# STC8a.net
KiCad netlist of a schematic drawn in Altium Designer
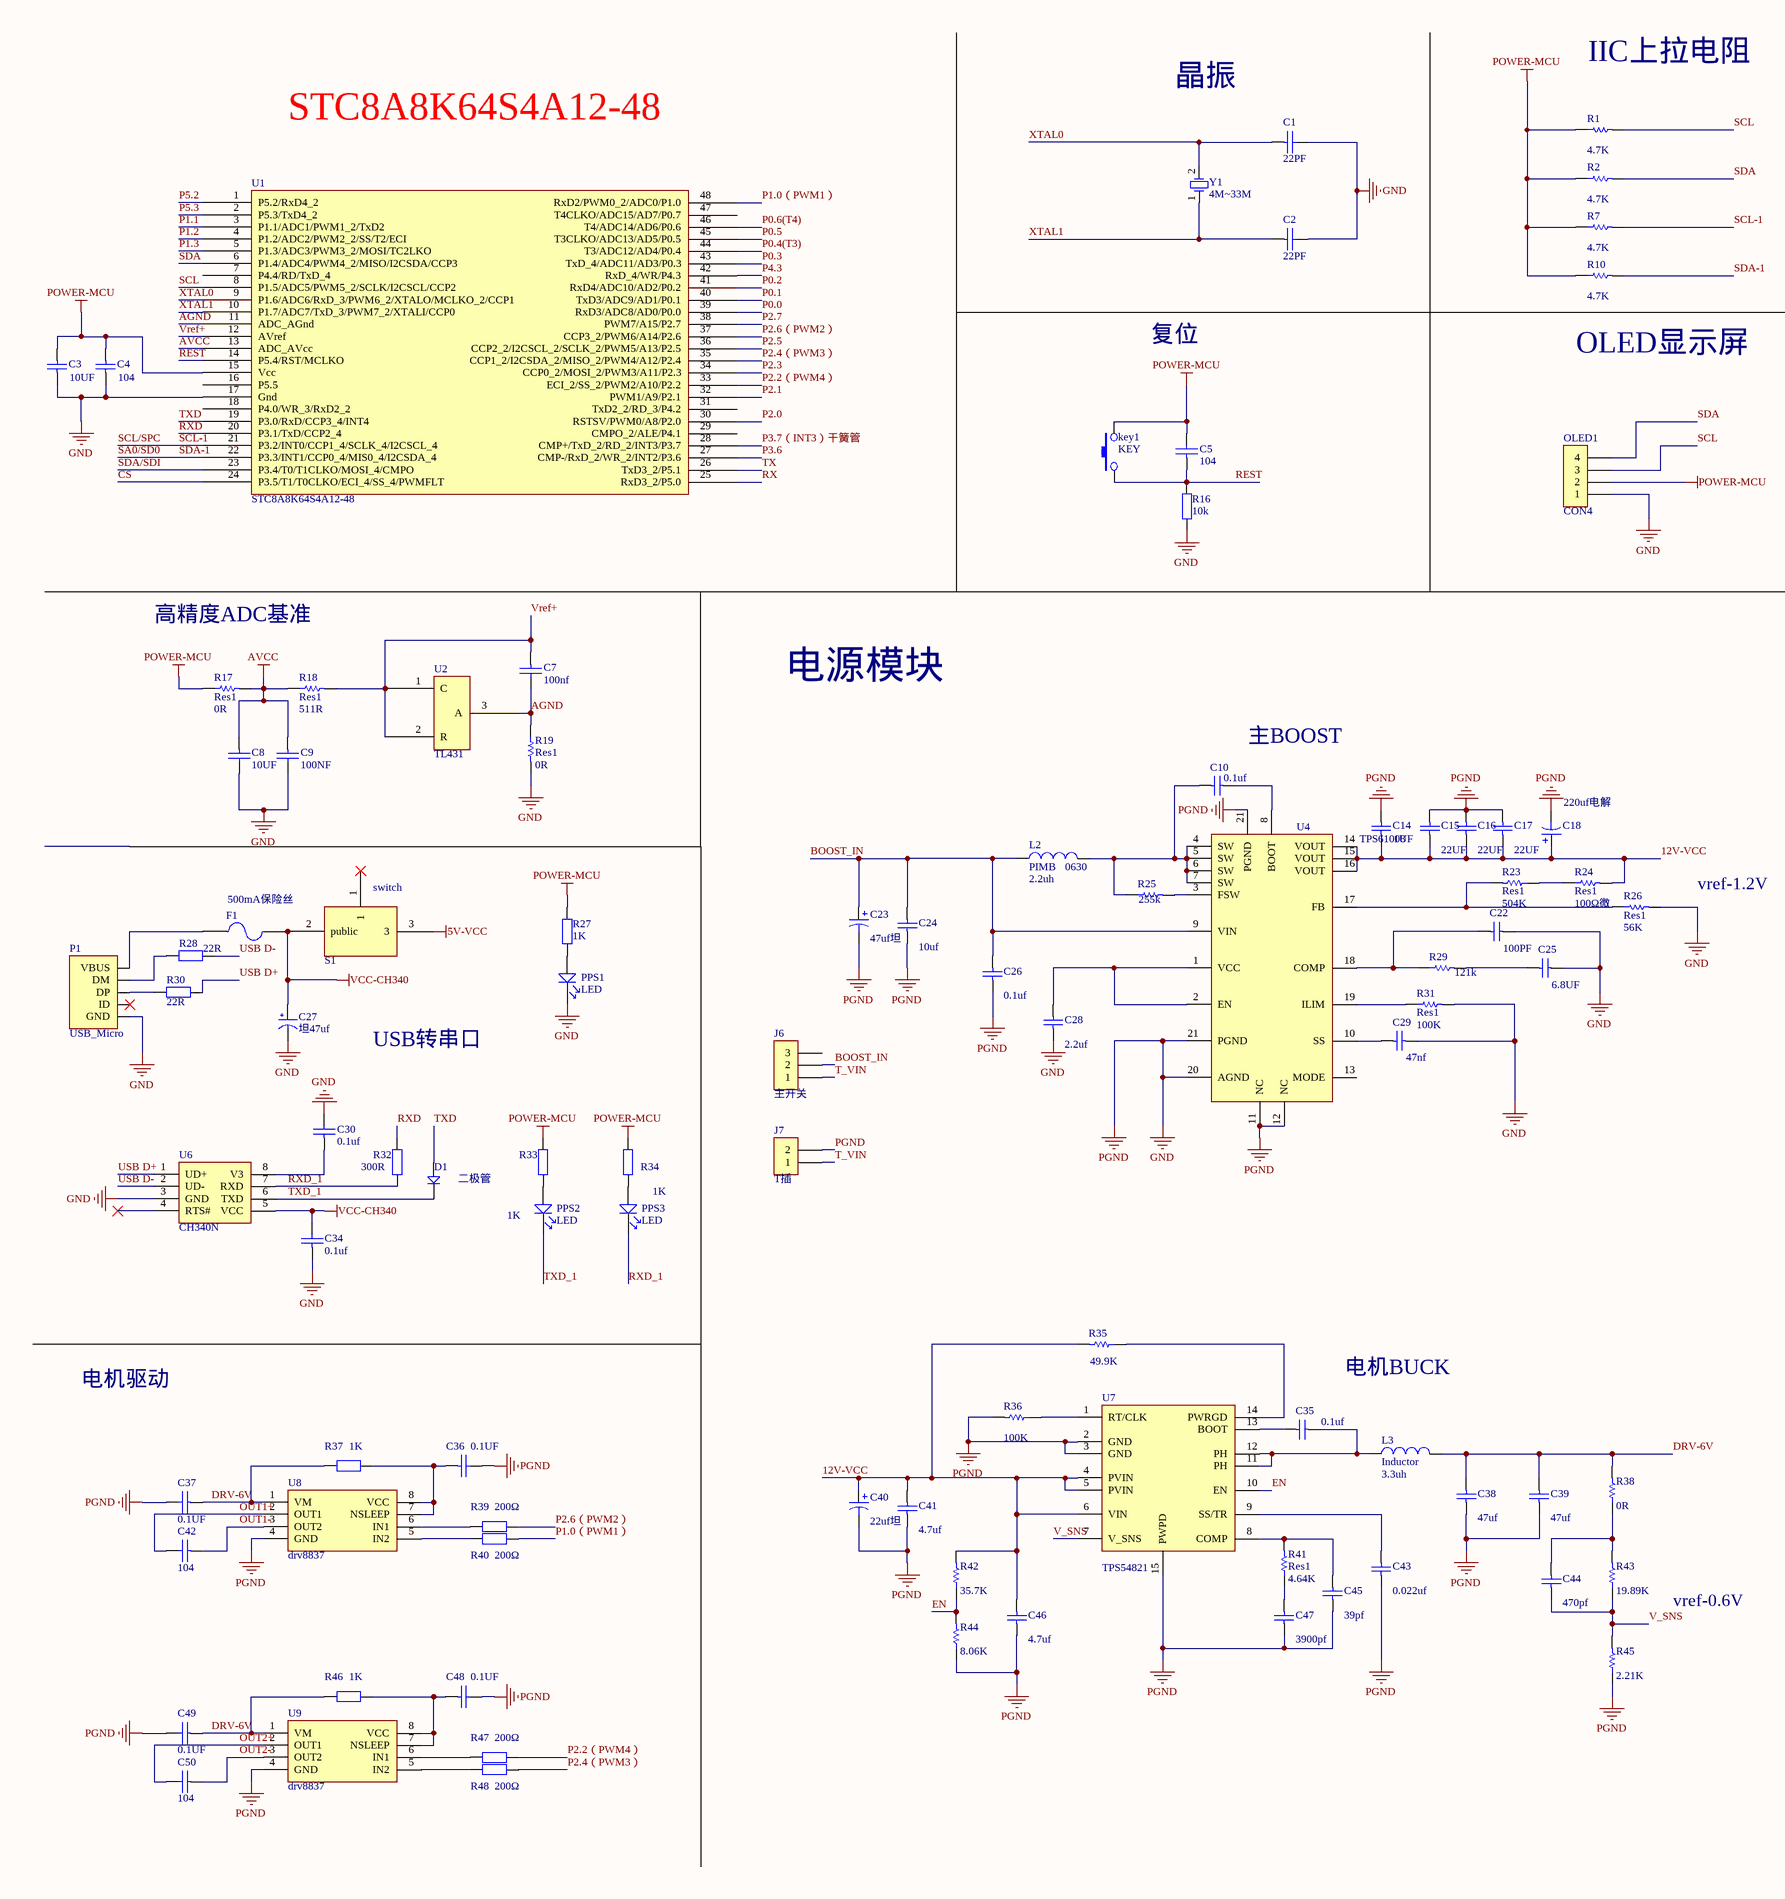
[diagram p0: STC8a.SchDoc, left]
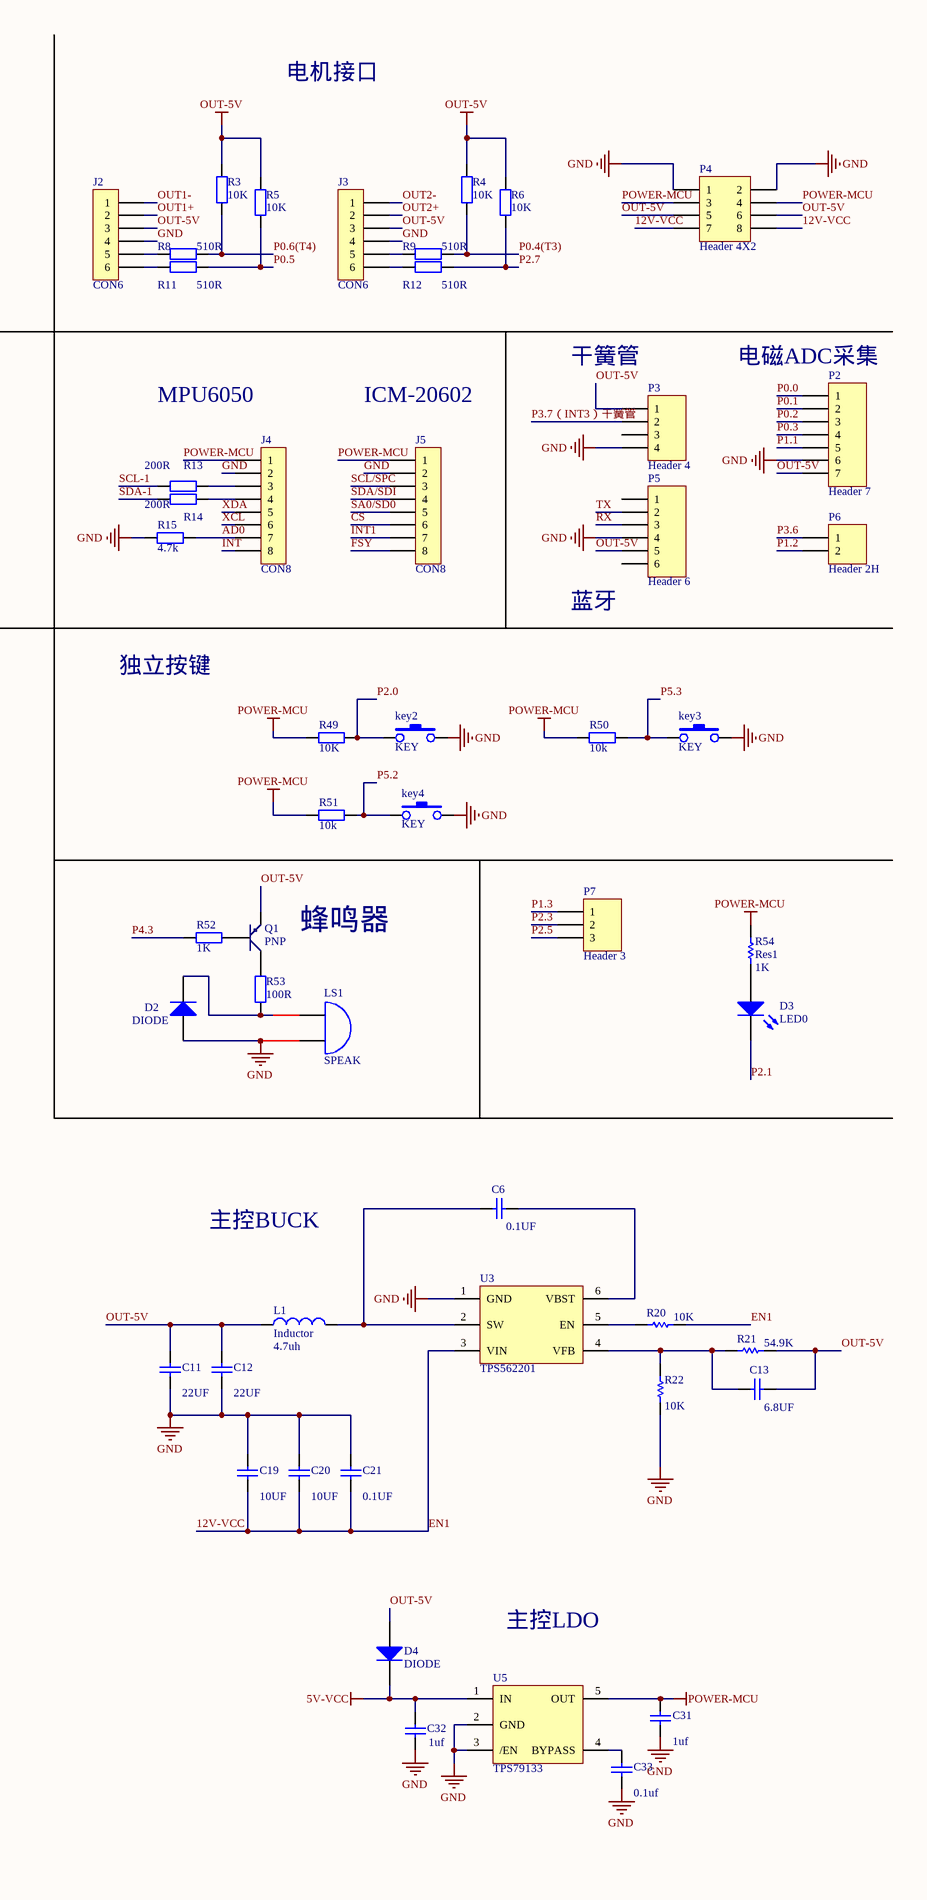
[diagram p1: STC8a.SchDoc, right]

(export (version "E")
  (design (tool "Eeschema 10.0.6"))
  (components
    (comp (ref "C1") (value "22PF") (footprint "0603-C") (libsource (lib "XH-Library") (part "CAP_0805")))
    (comp (ref "C2") (value "22PF") (footprint "0603-C") (libsource (lib "XH-Library") (part "CAP_0805")))
    (comp (ref "C3")
      (value "10UF")
      (footprint "0603-C")
      (description "Capacitor")
      (fields (field (name "PUBLISHER") "Altium Limited"))
      (libsource (lib "Miscellaneous Devices") (part "Cap"))
    )
    (comp (ref "C4")
      (value "104")
      (footprint "0603-C")
      (description "Capacitor")
      (fields (field (name "PUBLISHER") "Altium Limited"))
      (libsource (lib "Miscellaneous Devices") (part "Cap"))
    )
    (comp (ref "C5") (value "104") (footprint "0603-C") (libsource (lib "MINE") (part "CAP_0805")))
    (comp (ref "C6")
      (value "0.1UF")
      (footprint "0603-c")
      (description "Capacitor")
      (fields (field (name "PUBLISHER") "Altium Limited"))
      (libsource (lib "Miscellaneous Devices") (part "Cap"))
    )
    (comp (ref "C7") (value "100nf") (footprint "0603-C") (libsource (lib "自创(1)(1)") (part "CAP")))
    (comp (ref "C8") (value "10UF") (footprint "0603-C") (libsource (lib "自创(1)(1)") (part "CAP")))
    (comp (ref "C9") (value "100NF") (footprint "0603-C") (libsource (lib "自创(1)(1)") (part "CAP")))
    (comp (ref "C10")
      (value "0.1uf")
      (footprint "0603-c")
      (description "Capacitor")
      (fields (field (name "PUBLISHER") "Altium Limited"))
      (libsource (lib "Miscellaneous Devices") (part "Cap"))
    )
    (comp (ref "C11")
      (value "22UF")
      (footprint "1206")
      (description "Capacitor")
      (fields (field (name "PUBLISHER") "Altium Limited"))
      (libsource (lib "Miscellaneous Devices") (part "Cap"))
    )
    (comp (ref "C12")
      (value "22UF")
      (footprint "1206")
      (description "Capacitor")
      (fields (field (name "PUBLISHER") "Altium Limited"))
      (libsource (lib "Miscellaneous Devices") (part "Cap"))
    )
    (comp (ref "C13")
      (value "6.8UF")
      (footprint "0603-c")
      (description "Capacitor")
      (fields (field (name "PUBLISHER") "Altium Limited"))
      (libsource (lib "Miscellaneous Devices") (part "Cap"))
    )
    (comp (ref "C14")
      (value "1UF")
      (footprint "0805C")
      (description "Capacitor")
      (fields (field (name "PUBLISHER") "Altium Limited"))
      (libsource (lib "Miscellaneous Devices") (part "Cap"))
    )
    (comp (ref "C15")
      (value "22UF")
      (footprint "1206")
      (description "Capacitor")
      (fields (field (name "PUBLISHER") "Altium Limited"))
      (libsource (lib "Miscellaneous Devices") (part "Cap"))
    )
    (comp (ref "C16")
      (value "22UF")
      (footprint "1206")
      (description "Capacitor")
      (fields (field (name "PUBLISHER") "Altium Limited"))
      (libsource (lib "Miscellaneous Devices") (part "Cap"))
    )
    (comp (ref "C17")
      (value "22UF")
      (footprint "1206")
      (description "Capacitor")
      (fields (field (name "PUBLISHER") "Altium Limited"))
      (libsource (lib "Miscellaneous Devices") (part "Cap"))
    )
    (comp (ref "C18")
      (value "220uf电解")
      (footprint "CC88")
      (description "Polarized Capacitor (Radial)")
      (fields (field (name "PUBLISHER") "Altium Limited"))
      (libsource (lib "Miscellaneous Devices") (part "Cap Pol1"))
    )
    (comp (ref "C19")
      (value "10UF")
      (footprint "0805c")
      (description "Capacitor")
      (fields (field (name "PUBLISHER") "Altium Limited"))
      (libsource (lib "Miscellaneous Devices") (part "Cap"))
    )
    (comp (ref "C20")
      (value "10UF")
      (footprint "0805c")
      (description "Capacitor")
      (fields (field (name "PUBLISHER") "Altium Limited"))
      (libsource (lib "Miscellaneous Devices") (part "Cap"))
    )
    (comp (ref "C21")
      (value "0.1UF")
      (footprint "0805c")
      (description "Capacitor")
      (fields (field (name "PUBLISHER") "Altium Limited"))
      (libsource (lib "Miscellaneous Devices") (part "Cap"))
    )
    (comp (ref "C22")
      (value "100PF")
      (footprint "0603-C")
      (description "Capacitor")
      (fields (field (name "PUBLISHER") "Altium Limited"))
      (libsource (lib "Miscellaneous Devices") (part "Cap"))
    )
    (comp (ref "C23")
      (value "47uf坦")
      (footprint "1206")
      (description "Polarized Capacitor (Radial)")
      (fields (field (name "PUBLISHER") "Altium Limited"))
      (libsource (lib "Miscellaneous Devices") (part "Cap Pol1"))
    )
    (comp (ref "C24")
      (value "10uf")
      (footprint "0805-c")
      (description "Capacitor")
      (fields (field (name "PUBLISHER") "Altium Limited"))
      (libsource (lib "Miscellaneous Devices") (part "Cap"))
    )
    (comp (ref "C25")
      (value "6.8UF")
      (footprint "0603-C")
      (description "Capacitor")
      (fields (field (name "PUBLISHER") "Altium Limited"))
      (libsource (lib "Miscellaneous Devices") (part "Cap"))
    )
    (comp (ref "C26")
      (value "0.1uf")
      (footprint "0603-c")
      (description "Capacitor")
      (fields (field (name "PUBLISHER") "Altium Limited"))
      (libsource (lib "Miscellaneous Devices") (part "Cap"))
    )
    (comp (ref "C27") (value "坦47uf") (footprint "0805-C") (libsource (lib "MINE") (part "CAP")))
    (comp (ref "C28")
      (value "2.2uf")
      (footprint "0603-c")
      (description "Capacitor")
      (fields (field (name "PUBLISHER") "Altium Limited"))
      (libsource (lib "Miscellaneous Devices") (part "Cap"))
    )
    (comp (ref "C29")
      (value "47nf")
      (footprint "0603-C")
      (description "Capacitor")
      (fields (field (name "PUBLISHER") "Altium Limited"))
      (libsource (lib "Miscellaneous Devices") (part "Cap"))
    )
    (comp (ref "C30") (value "0.1uf") (footprint "0603-C") (libsource (lib "自创(1)(1)") (part "CAP")))
    (comp (ref "C31")
      (value "1uf")
      (footprint "0603-C")
      (description "Capacitor")
      (fields (field (name "PUBLISHER") "Altium Limited"))
      (libsource (lib "Miscellaneous Devices") (part "Cap"))
    )
    (comp (ref "C32")
      (value "1uf")
      (footprint "0603-C")
      (description "Capacitor")
      (fields (field (name "PUBLISHER") "Altium Limited"))
      (libsource (lib "Miscellaneous Devices") (part "Cap"))
    )
    (comp (ref "C33")
      (value "0.1uf")
      (footprint "0603-C")
      (description "Capacitor")
      (fields (field (name "PUBLISHER") "Altium Limited"))
      (libsource (lib "Miscellaneous Devices") (part "Cap"))
    )
    (comp (ref "C34") (value "0.1uf") (footprint "0603-C") (libsource (lib "自创(1)(1)") (part "CAP")))
    (comp (ref "C35")
      (value "0.1uf")
      (footprint "0603-c")
      (description "Capacitor")
      (fields (field (name "PUBLISHER") "Altium Limited"))
      (libsource (lib "Miscellaneous Devices") (part "Cap"))
    )
    (comp (ref "C36") (value "0.1UF") (footprint "0603-r") (libsource (lib "MINE") (part "CAP_0805")))
    (comp (ref "C37") (value "0.1UF") (footprint "0603-r") (libsource (lib "MINE") (part "CAP_0805")))
    (comp (ref "C38")
      (value "47uf")
      (footprint "1206")
      (description "Capacitor")
      (fields (field (name "PUBLISHER") "Altium Limited"))
      (libsource (lib "Miscellaneous Devices") (part "Cap"))
    )
    (comp (ref "C39")
      (value "47uf")
      (footprint "1206")
      (description "Capacitor")
      (fields (field (name "PUBLISHER") "Altium Limited"))
      (libsource (lib "Miscellaneous Devices") (part "Cap"))
    )
    (comp (ref "C40")
      (value "22uf坦")
      (footprint "1206")
      (description "Polarized Capacitor (Radial)")
      (fields (field (name "PUBLISHER") "Altium Limited"))
      (libsource (lib "Miscellaneous Devices") (part "Cap Pol1"))
    )
    (comp (ref "C41")
      (value "4.7uf")
      (footprint "0805c")
      (description "Capacitor")
      (fields (field (name "PUBLISHER") "Altium Limited"))
      (libsource (lib "Miscellaneous Devices") (part "Cap"))
    )
    (comp (ref "C42") (value "104") (footprint "0603-r") (libsource (lib "MINE") (part "CAP_0805")))
    (comp (ref "C43")
      (value "0.022uf")
      (footprint "0603-r")
      (description "Capacitor")
      (fields (field (name "PUBLISHER") "Altium Limited"))
      (libsource (lib "Miscellaneous Devices") (part "Cap"))
    )
    (comp (ref "C44")
      (value "470pf")
      (footprint "0603-c")
      (description "Capacitor")
      (fields (field (name "PUBLISHER") "Altium Limited"))
      (libsource (lib "Miscellaneous Devices") (part "Cap"))
    )
    (comp (ref "C45")
      (value "39pf")
      (footprint "0603-c")
      (description "Capacitor")
      (fields (field (name "PUBLISHER") "Altium Limited"))
      (libsource (lib "Miscellaneous Devices") (part "Cap"))
    )
    (comp (ref "C46")
      (value "4.7uf")
      (footprint "0805r")
      (description "Capacitor")
      (fields (field (name "PUBLISHER") "Altium Limited"))
      (libsource (lib "Miscellaneous Devices") (part "Cap"))
    )
    (comp (ref "C47")
      (value "3900pf")
      (footprint "0603-c")
      (description "Capacitor")
      (fields (field (name "PUBLISHER") "Altium Limited"))
      (libsource (lib "Miscellaneous Devices") (part "Cap"))
    )
    (comp (ref "C48") (value "0.1UF") (footprint "0603-r") (libsource (lib "MINE") (part "CAP_0805")))
    (comp (ref "C49") (value "0.1UF") (footprint "0603-r") (libsource (lib "MINE") (part "CAP_0805")))
    (comp (ref "C50") (value "104") (footprint "0603-r") (libsource (lib "MINE") (part "CAP_0805")))
    (comp (ref "D1")
      (value "二极管")
      (footprint "DIODE_SOP")
      (description "1N4148")
      (libsource (lib "MINE") (part "D_1"))
    )
    (comp (ref "D2")
      (value "DIODE")
      (footprint "DIODE_SOP - duplicate1")
      (description "Default Diode")
      (fields (field (name "PUBLISHER") "Altium Limited"))
      (libsource (lib "MINE") (part "Diode_1_2"))
    )
    (comp (ref "D3")
      (value "LED0")
      (footprint "0805-LED")
      (description "Typical INFRARED GaAs LED")
      (fields (field (name "PUBLISHER") "Altium Limited"))
      (libsource (lib "Miscellaneous Devices") (part "LED0"))
    )
    (comp (ref "D4")
      (value "DIODE")
      (footprint "DIODE_SOP - duplicate1")
      (description "Default Diode")
      (fields (field (name "PUBLISHER") "Altium Limited"))
      (libsource (lib "MINE") (part "Diode_1_2"))
    )
    (comp (ref "F1")
      (value "500mA保险丝")
      (footprint "0805 - duplicate")
      (description "Fuse")
      (fields (field (name "PUBLISHER") "Altium Limited"))
      (libsource (lib "MINE") (part "Fuse 2"))
    )
    (comp (ref "J2") (value "CON6") (footprint "XH6-1.5x1.5") (libsource (lib "MYSchlib1") (part "CON6")))
    (comp (ref "J3") (value "CON6") (footprint "XH6-1.5x1.5") (libsource (lib "MYSchlib1") (part "CON6")))
    (comp (ref "J4") (value "CON8") (footprint "HDR1X8") (libsource (lib "MYSchlib1") (part "CON8")))
    (comp (ref "J5") (value "CON8") (footprint "HDR1X8") (libsource (lib "MYSchlib1") (part "CON8")))
    (comp (ref "J6") (value "主开关") (footprint "拨动开关") (libsource (lib "MYSchlib1") (part "CON3")))
    (comp (ref "J7") (value "T插") (footprint "T型头") (libsource (lib "MYSchlib1") (part "CON2")))
    (comp (ref "key1") (value "KEY") (footprint "KEY") (libsource (lib "MINE") (part "KEY")))
    (comp (ref "key2") (value "KEY") (footprint "KEY") (libsource (lib "MINE") (part "KEY")))
    (comp (ref "key3") (value "KEY") (footprint "KEY") (libsource (lib "MINE") (part "KEY")))
    (comp (ref "key4") (value "KEY") (footprint "KEY") (libsource (lib "MINE") (part "KEY")))
    (comp (ref "L1")
      (value "Inductor")
      (footprint "L8*8")
      (fields (field (name "ALTIUM_VALUE") "4.7uh") (field (name "PUBLISHER") "Altium Limited"))
      (libsource (lib "Miscellaneous Devices") (part "Inductor"))
    )
    (comp (ref "L2")
      (value "PIMB   0630")
      (footprint "L8*8")
      (description "Inductor")
      (fields (field (name "ALTIUM_VALUE") "2.2uh") (field (name "PUBLISHER") "Altium Limited"))
      (libsource (lib "Miscellaneous Devices") (part "Inductor"))
    )
    (comp (ref "L3")
      (value "Inductor")
      (footprint "L8*8")
      (fields (field (name "ALTIUM_VALUE") "3.3uh") (field (name "PUBLISHER") "Altium Limited"))
      (libsource (lib "Miscellaneous Devices") (part "Inductor"))
    )
    (comp (ref "LS1")
      (value "SPEAK")
      (footprint "BELL-5")
      (description "Electrical Bell")
      (fields (field (name "PUBLISHER") "Altium Limited"))
      (libsource (lib "MINE") (part "SPEAK"))
    )
    (comp (ref "OLED1") (value "CON4") (footprint "HDR1X4") (libsource (lib "MYSchlib1") (part "CON4")))
    (comp (ref "P1")
      (value "USB_Micro")
      (footprint "USB_MINI - duplicate")
      (description "USB")
      (libsource (lib "MINE") (part "USB_Micro"))
    )
    (comp (ref "P2")
      (value "Header 7")
      (footprint "HDR1X7")
      (description "Header, 7-Pin")
      (fields (field (name "PUBLISHER") "Altium Limited"))
      (libsource (lib "Miscellaneous Connectors") (part "Header 7"))
    )
    (comp (ref "P3")
      (value "Header 4")
      (footprint "HDR1X4")
      (description "Header, 4-Pin")
      (fields (field (name "PUBLISHER") "Altium Limited"))
      (libsource (lib "Miscellaneous Connectors") (part "Header 4"))
    )
    (comp (ref "P4")
      (value "Header 4X2")
      (footprint "HDR2X4")
      (description "Header, 4-Pin, Dual row")
      (fields (field (name "PUBLISHER") "Altium Limited"))
      (libsource (lib "Miscellaneous Connectors") (part "Header 4X2"))
    )
    (comp (ref "P5")
      (value "Header 6")
      (footprint "HDR1X6")
      (description "Header, 6-Pin")
      (fields (field (name "PUBLISHER") "Altium Limited"))
      (libsource (lib "Miscellaneous Connectors") (part "Header 6"))
    )
    (comp (ref "P6")
      (value "Header 2H")
      (footprint "HDR1X2")
      (description "Header, 2-Pin, Right Angle")
      (fields (field (name "PUBLISHER") "Altium Limited"))
      (libsource (lib "Miscellaneous Connectors") (part "Header 2H"))
    )
    (comp (ref "P7")
      (value "Header 3")
      (footprint "HDR1X3")
      (description "Header, 3-Pin")
      (fields (field (name "PUBLISHER") "Altium Limited"))
      (libsource (lib "Miscellaneous Connectors") (part "Header 3"))
    )
    (comp (ref "PPS1") (value "LED") (footprint "0805-LED") (libsource (lib "MINE") (part "LED")))
    (comp (ref "PPS2") (value "LED") (footprint "0805-LED") (libsource (lib "MINE") (part "LED")))
    (comp (ref "PPS3") (value "LED") (footprint "0805-LED") (libsource (lib "MINE") (part "LED")))
    (comp (ref "Q1")
      (value "PNP")
      (footprint "SOT-23R")
      (description "8550/BCW68")
      (libsource (lib "MINE") (part "PNP_5"))
    )
    (comp (ref "R1")
      (value "4.7K")
      (footprint "0603-R")
      (description "Resistor")
      (fields (field (name "PUBLISHER") "Altium Limited"))
      (libsource (lib "MYSchlib1") (part "Res1"))
    )
    (comp (ref "R2")
      (value "4.7K")
      (footprint "0603-R")
      (description "Resistor")
      (fields (field (name "PUBLISHER") "Altium Limited"))
      (libsource (lib "MYSchlib1") (part "Res1"))
    )
    (comp (ref "R3")
      (value "10K")
      (footprint "0603-R")
      (description "Resistor")
      (fields (field (name "PUBLISHER") "Altium Limited"))
      (libsource (lib "") (part "RES_2"))
    )
    (comp (ref "R4")
      (value "10K")
      (footprint "0603-R")
      (description "Resistor")
      (fields (field (name "PUBLISHER") "Altium Limited"))
      (libsource (lib "") (part "RES_2"))
    )
    (comp (ref "R5")
      (value "10K")
      (footprint "0603-R")
      (description "Resistor")
      (fields (field (name "PUBLISHER") "Altium Limited"))
      (libsource (lib "") (part "RES_2"))
    )
    (comp (ref "R6")
      (value "10K")
      (footprint "0603-R")
      (description "Resistor")
      (fields (field (name "PUBLISHER") "Altium Limited"))
      (libsource (lib "") (part "RES_2"))
    )
    (comp (ref "R7")
      (value "4.7K")
      (footprint "0603-R")
      (description "Resistor")
      (fields (field (name "PUBLISHER") "Altium Limited"))
      (libsource (lib "MYSchlib1") (part "Res1"))
    )
    (comp (ref "R8")
      (value "510R")
      (footprint "0603-R")
      (description "Resistor")
      (fields (field (name "PUBLISHER") "Altium Limited"))
      (libsource (lib "MINE") (part "RES"))
    )
    (comp (ref "R9")
      (value "510R")
      (footprint "0603-R")
      (description "Resistor")
      (fields (field (name "PUBLISHER") "Altium Limited"))
      (libsource (lib "MINE") (part "RES"))
    )
    (comp (ref "R10")
      (value "4.7K")
      (footprint "0603-R")
      (description "Resistor")
      (fields (field (name "PUBLISHER") "Altium Limited"))
      (libsource (lib "MYSchlib1") (part "Res1"))
    )
    (comp (ref "R11")
      (value "510R")
      (footprint "0603-R")
      (description "Resistor")
      (fields (field (name "PUBLISHER") "Altium Limited"))
      (libsource (lib "MINE") (part "RES"))
    )
    (comp (ref "R12")
      (value "510R")
      (footprint "0603-R")
      (description "Resistor")
      (fields (field (name "PUBLISHER") "Altium Limited"))
      (libsource (lib "MINE") (part "RES"))
    )
    (comp (ref "R13")
      (value "200R")
      (footprint "0603-R")
      (description "Resistor")
      (fields (field (name "PUBLISHER") "Altium Limited"))
      (libsource (lib "") (part "RES_3"))
    )
    (comp (ref "R14")
      (value "200R")
      (footprint "0603-R")
      (description "Resistor")
      (fields (field (name "PUBLISHER") "Altium Limited"))
      (libsource (lib "") (part "RES_3"))
    )
    (comp (ref "R15")
      (value "4.7k")
      (footprint "0603-R")
      (description "Resistor")
      (fields (field (name "PUBLISHER") "Altium Limited"))
      (libsource (lib "") (part "RES_3"))
    )
    (comp (ref "R16")
      (value "10k")
      (footprint "0603-R")
      (description "Resistor")
      (fields (field (name "PUBLISHER") "Altium Limited"))
      (libsource (lib "") (part "RES_1"))
    )
    (comp (ref "R17")
      (value "Res1")
      (footprint "0603-R")
      (description "Resistor")
      (fields (field (name "ALTIUM_VALUE") "0R") (field (name "PUBLISHER") "Altium Limited"))
      (libsource (lib "自创(1)(1)") (part "Res1"))
    )
    (comp (ref "R18")
      (value "Res1")
      (footprint "0603-R")
      (description "Resistor")
      (fields (field (name "ALTIUM_VALUE") "511R") (field (name "PUBLISHER") "Altium Limited"))
      (libsource (lib "自创(1)(1)") (part "Res1"))
    )
    (comp (ref "R19")
      (value "Res1")
      (footprint "0603-R")
      (description "Resistor")
      (fields (field (name "ALTIUM_VALUE") "0R") (field (name "PUBLISHER") "Altium Limited"))
      (libsource (lib "自创(1)(1)") (part "Res1"))
    )
    (comp (ref "R20")
      (value "10K")
      (footprint "0603-r")
      (description "Resistor")
      (fields (field (name "PUBLISHER") "Altium Limited"))
      (libsource (lib "Miscellaneous Devices") (part "Res1"))
    )
    (comp (ref "R21")
      (value "54.9K")
      (footprint "0603-r")
      (description "Resistor")
      (fields (field (name "PUBLISHER") "Altium Limited"))
      (libsource (lib "Miscellaneous Devices") (part "Res1"))
    )
    (comp (ref "R22")
      (value "10K")
      (footprint "0603-r")
      (description "Resistor")
      (fields (field (name "PUBLISHER") "Altium Limited"))
      (libsource (lib "Miscellaneous Devices") (part "Res1"))
    )
    (comp (ref "R23")
      (value "Res1")
      (footprint "0603-R")
      (description "Resistor")
      (fields (field (name "ALTIUM_VALUE") "504K") (field (name "PUBLISHER") "Altium Limited"))
      (libsource (lib "Miscellaneous Devices") (part "Res1"))
    )
    (comp (ref "R24")
      (value "Res1")
      (footprint "0603-R")
      (description "Resistor")
      (fields (field (name "ALTIUM_VALUE") "100Ω微") (field (name "PUBLISHER") "Altium Limited"))
      (libsource (lib "Miscellaneous Devices") (part "Res1"))
    )
    (comp (ref "R25")
      (value "255k")
      (footprint "0603-r")
      (description "Resistor")
      (fields (field (name "PUBLISHER") "Altium Limited"))
      (libsource (lib "Miscellaneous Devices") (part "Res1"))
    )
    (comp (ref "R26")
      (value "Res1")
      (footprint "0603-R")
      (description "Resistor")
      (fields (field (name "ALTIUM_VALUE") "56K") (field (name "PUBLISHER") "Altium Limited"))
      (libsource (lib "Miscellaneous Devices") (part "Res1"))
    )
    (comp (ref "R27")
      (value "1K")
      (footprint "0603-R")
      (description "Resistor")
      (fields (field (name "PUBLISHER") "Altium Limited"))
      (libsource (lib "") (part "RES_2"))
    )
    (comp (ref "R28")
      (value "22R")
      (footprint "0603-R")
      (description "Resistor")
      (fields (field (name "PUBLISHER") "Altium Limited"))
      (libsource (lib "MINE") (part "RES"))
    )
    (comp (ref "R29")
      (value "121k")
      (footprint "0603-R")
      (description "Resistor")
      (fields (field (name "PUBLISHER") "Altium Limited"))
      (libsource (lib "Miscellaneous Devices") (part "Res1"))
    )
    (comp (ref "R30")
      (value "22R")
      (footprint "0603-R")
      (description "Resistor")
      (fields (field (name "PUBLISHER") "Altium Limited"))
      (libsource (lib "MINE") (part "RES"))
    )
    (comp (ref "R31")
      (value "Res1")
      (footprint "0603-R")
      (description "Resistor")
      (fields (field (name "ALTIUM_VALUE") "100K") (field (name "PUBLISHER") "Altium Limited"))
      (libsource (lib "Miscellaneous Devices") (part "Res1"))
    )
    (comp (ref "R32")
      (value "300R")
      (footprint "0603-R")
      (description "Resistor")
      (fields (field (name "PUBLISHER") "Altium Limited"))
      (libsource (lib "") (part "RES_1"))
    )
    (comp (ref "R33")
      (value "1K")
      (footprint "0603-R")
      (description "Resistor")
      (fields (field (name "PUBLISHER") "Altium Limited"))
      (libsource (lib "") (part "RES_1"))
    )
    (comp (ref "R34")
      (value "1K")
      (footprint "0603-R")
      (description "Resistor")
      (fields (field (name "PUBLISHER") "Altium Limited"))
      (libsource (lib "") (part "RES_1"))
    )
    (comp (ref "R35")
      (value "49.9K")
      (footprint "0603-r")
      (description "Resistor")
      (fields (field (name "PUBLISHER") "Altium Limited"))
      (libsource (lib "Miscellaneous Devices") (part "Res1"))
    )
    (comp (ref "R36")
      (value "100K")
      (footprint "0603-r")
      (description "Resistor")
      (fields (field (name "PUBLISHER") "Altium Limited"))
      (libsource (lib "Miscellaneous Devices") (part "Res1"))
    )
    (comp (ref "R37")
      (value "1K")
      (footprint "0603-r")
      (description "Resistor")
      (fields (field (name "PUBLISHER") "Altium Limited"))
      (libsource (lib "") (part "RES_3"))
    )
    (comp (ref "R38")
      (value "0R")
      (footprint "0603-r")
      (description "Resistor")
      (fields (field (name "PUBLISHER") "Altium Limited"))
      (libsource (lib "Miscellaneous Devices") (part "Res1"))
    )
    (comp (ref "R39")
      (value "200Ω")
      (footprint "0603-r")
      (description "Resistor")
      (fields (field (name "PUBLISHER") "Altium Limited"))
      (libsource (lib "") (part "RES_3"))
    )
    (comp (ref "R40")
      (value "200Ω")
      (footprint "0603-r")
      (description "Resistor")
      (fields (field (name "PUBLISHER") "Altium Limited"))
      (libsource (lib "") (part "RES_3"))
    )
    (comp (ref "R41")
      (value "Res1")
      (footprint "0603-r")
      (description "Resistor")
      (fields (field (name "ALTIUM_VALUE") "4.64K") (field (name "PUBLISHER") "Altium Limited"))
      (libsource (lib "Miscellaneous Devices") (part "Res1"))
    )
    (comp (ref "R42")
      (value "35.7K")
      (footprint "0603-r")
      (description "Resistor")
      (fields (field (name "PUBLISHER") "Altium Limited"))
      (libsource (lib "Miscellaneous Devices") (part "Res1"))
    )
    (comp (ref "R43")
      (value "19.89K")
      (footprint "0603-r")
      (description "Resistor")
      (fields (field (name "PUBLISHER") "Altium Limited"))
      (libsource (lib "Miscellaneous Devices") (part "Res1"))
    )
    (comp (ref "R44")
      (value "8.06K")
      (footprint "0603-r")
      (description "Resistor")
      (fields (field (name "PUBLISHER") "Altium Limited"))
      (libsource (lib "Miscellaneous Devices") (part "Res1"))
    )
    (comp (ref "R45")
      (value "2.21K")
      (footprint "0603-r")
      (description "Resistor")
      (fields (field (name "PUBLISHER") "Altium Limited"))
      (libsource (lib "Miscellaneous Devices") (part "Res1"))
    )
    (comp (ref "R46")
      (value "1K")
      (footprint "0603-r")
      (description "Resistor")
      (fields (field (name "PUBLISHER") "Altium Limited"))
      (libsource (lib "") (part "RES_3"))
    )
    (comp (ref "R47")
      (value "200Ω")
      (footprint "0603-r")
      (description "Resistor")
      (fields (field (name "PUBLISHER") "Altium Limited"))
      (libsource (lib "") (part "RES_3"))
    )
    (comp (ref "R48")
      (value "200Ω")
      (footprint "0603-r")
      (description "Resistor")
      (fields (field (name "PUBLISHER") "Altium Limited"))
      (libsource (lib "") (part "RES_3"))
    )
    (comp (ref "R49")
      (value "10K")
      (footprint "0603-R")
      (description "Resistor")
      (fields (field (name "PUBLISHER") "Altium Limited"))
      (libsource (lib "MINE") (part "RES"))
    )
    (comp (ref "R50")
      (value "10k")
      (footprint "0603-R")
      (description "Resistor")
      (fields (field (name "PUBLISHER") "Altium Limited"))
      (libsource (lib "MINE") (part "RES"))
    )
    (comp (ref "R51")
      (value "10k")
      (footprint "0603-R")
      (description "Resistor")
      (fields (field (name "PUBLISHER") "Altium Limited"))
      (libsource (lib "MINE") (part "RES"))
    )
    (comp (ref "R52")
      (value "1K")
      (footprint "0603-R")
      (description "Resistor")
      (fields (field (name "Comment") "1k"))
      (libsource (lib "MINE") (part "Res_0603"))
    )
    (comp (ref "R53")
      (value "100R")
      (footprint "0603-R")
      (description "Resistor")
      (libsource (lib "") (part "Res_0603_1"))
    )
    (comp (ref "R54")
      (value "Res1")
      (footprint "0603-R")
      (description "Resistor")
      (fields (field (name "ALTIUM_VALUE") "1K") (field (name "PUBLISHER") "Altium Limited"))
      (libsource (lib "Miscellaneous Devices") (part "Res1"))
    )
    (comp (ref "S1")
      (value "switch")
      (footprint "HDR1X3")
      (description "Switch")
      (fields (field (name "PUBLISHER") "Altium Limited"))
      (libsource (lib "51_base") (part "SW DPDT"))
    )
    (comp (ref "U1")
      (value "STC8A8K64S4A12-48")
      (footprint "LQFP48S")
      (libsource (lib "Schlib1") (part "STC8A8K64S4A12-48"))
    )
    (comp (ref "U2")
      (value "TL431")
      (footprint "SOT-23")
      (libsource (lib "STC8G2K64S4-LQFP48") (part "TL431"))
    )
    (comp (ref "U3")
      (value "TPS562201")
      (footprint "LC-SOT-23-6")
      (libsource (lib "Schlib1") (part "TPS562201"))
    )
    (comp (ref "U4") (value "TPS61008") (footprint "TPS61088改") (libsource (lib "Schlib1") (part "TPS61008")))
    (comp (ref "U5")
      (value "TPS79133")
      (footprint "LC-SOT-23-5")
      (libsource (lib "Schlib1") (part "TPS79133"))
    )
    (comp (ref "U6") (value "CH340N") (footprint "SOP-8") (libsource (lib "Schlib1") (part "CH340N")))
    (comp (ref "U7") (value "TPS54821") (footprint "VQFN-14改") (libsource (lib "Schlib1") (part "TPS54821")))
    (comp (ref "U8")
      (value "drv8837")
      (footprint "wson-8-2X2改")
      (libsource (lib "Schlib1") (part "DRV8837DSGR"))
    )
    (comp (ref "U9")
      (value "drv8837")
      (footprint "wson-8-2X2改")
      (libsource (lib "Schlib1") (part "DRV8837DSGR"))
    )
    (comp (ref "Y1")
      (value "4M~33M")
      (footprint "XTAL_5032")
      (description "Crystal Oscillator")
      (fields (field (name "Comment") "XTAL_5032") (field (name "PUBLISHER") "Altium Limited"))
      (libsource (lib "XH-Library") (part "XTAL_5032"))
    )
  )
  (nets
    (net (code "1") (name "/12V-VCC") (class "Default")
      (node (ref "C14") (pin "2") (pinfunction "2_2") (pintype "passive"))
      (node (ref "C15") (pin "2") (pinfunction "2_2") (pintype "passive"))
      (node (ref "C16") (pin "2") (pinfunction "2_2") (pintype "passive"))
      (node (ref "C17") (pin "2") (pinfunction "2_2") (pintype "passive"))
      (node (ref "C18") (pin "1") (pinfunction "1_1") (pintype "passive"))
      (node (ref "C19") (pin "1") (pinfunction "1_1") (pintype "passive"))
      (node (ref "C20") (pin "1") (pinfunction "1_1") (pintype "passive"))
      (node (ref "C21") (pin "1") (pinfunction "1_1") (pintype "passive"))
      (node (ref "C40") (pin "1") (pinfunction "1_1") (pintype "passive"))
      (node (ref "C41") (pin "2") (pinfunction "2_2") (pintype "passive"))
      (node (ref "C46") (pin "2") (pinfunction "2_2") (pintype "passive"))
      (node (ref "P4") (pin "7") (pinfunction "7_7") (pintype "passive"))
      (node (ref "P4") (pin "8") (pinfunction "8_8") (pintype "passive"))
      (node (ref "R20") (pin "2") (pinfunction "2_2") (pintype "passive"))
      (node (ref "R24") (pin "2") (pinfunction "2_2") (pintype "passive"))
      (node (ref "R35") (pin "2") (pinfunction "2_2") (pintype "passive"))
      (node (ref "R42") (pin "2") (pinfunction "2_2") (pintype "passive"))
      (node (ref "U3") (pin "3") (pinfunction "VIN_3") (pintype "passive"))
      (node (ref "U4") (pin "14") (pinfunction "VOUT_14") (pintype "passive"))
      (node (ref "U4") (pin "15") (pinfunction "VOUT_15") (pintype "passive"))
      (node (ref "U4") (pin "16") (pinfunction "VOUT_16") (pintype "passive"))
      (node (ref "U7") (pin "4") (pinfunction "PVIN_4") (pintype "passive"))
      (node (ref "U7") (pin "5") (pinfunction "PVIN_5") (pintype "passive"))
      (node (ref "U7") (pin "6") (pinfunction "VIN_6") (pintype "passive"))
    )
    (net (code "2") (name "/AD0") (class "Default")
      (node (ref "J4") (pin "7") (pinfunction "7_7") (pintype "passive"))
      (node (ref "R15") (pin "1") (pinfunction "1_1") (pintype "passive"))
    )
    (net (code "3") (name "/AGND") (class "Default")
      (node (ref "C7") (pin "2") (pinfunction "2_2") (pintype "passive"))
      (node (ref "R19") (pin "1") (pinfunction "1_1") (pintype "passive"))
      (node (ref "U1") (pin "11") (pinfunction "ADC_AGnd_11") (pintype "passive"))
      (node (ref "U2") (pin "3") (pinfunction "A_3") (pintype "passive"))
    )
    (net (code "4") (name "/BOOST_IN") (class "Default")
      (node (ref "C23") (pin "1") (pinfunction "1_1") (pintype "passive"))
      (node (ref "C24") (pin "2") (pinfunction "2_2") (pintype "passive"))
      (node (ref "C26") (pin "2") (pinfunction "2_2") (pintype "passive"))
      (node (ref "J6") (pin "2") (pinfunction "2_2") (pintype "passive"))
      (node (ref "L2") (pin "1") (pinfunction "1_1") (pintype "passive"))
      (node (ref "U4") (pin "9") (pinfunction "VIN_9") (pintype "passive"))
    )
    (net (code "5") (name "/CS") (class "Default")
      (node (ref "J5") (pin "6") (pinfunction "6_6") (pintype "passive"))
      (node (ref "U1") (pin "24") (pinfunction "P3.5/T1/T0CLKO/ECI_4/SS_4/PWMFLT_24") (pintype "passive"))
    )
    (net (code "6") (name "/DRV-6V") (class "Default")
      (node (ref "C37") (pin "1") (pinfunction "1_1") (pintype "passive"))
      (node (ref "C38") (pin "2") (pinfunction "2_2") (pintype "passive"))
      (node (ref "C39") (pin "2") (pinfunction "2_2") (pintype "passive"))
      (node (ref "C49") (pin "1") (pinfunction "1_1") (pintype "passive"))
      (node (ref "L3") (pin "2") (pinfunction "2_2") (pintype "passive"))
      (node (ref "R37") (pin "2") (pinfunction "2_2") (pintype "passive"))
      (node (ref "R38") (pin "2") (pinfunction "2_2") (pintype "passive"))
      (node (ref "R46") (pin "2") (pinfunction "2_2") (pintype "passive"))
      (node (ref "U8") (pin "1") (pinfunction "VM_1") (pintype "passive"))
      (node (ref "U9") (pin "1") (pinfunction "VM_1") (pintype "passive"))
    )
    (net (code "7") (name "/EN") (class "Default")
      (node (ref "R42") (pin "1") (pinfunction "1_1") (pintype "passive"))
      (node (ref "R44") (pin "2") (pinfunction "2_2") (pintype "passive"))
      (node (ref "U7") (pin "10") (pinfunction "EN_10") (pintype "passive"))
    )
    (net (code "8") (name "/FSY") (class "Default")
      (node (ref "J5") (pin "8") (pinfunction "8_8") (pintype "passive"))
    )
    (net (code "9") (name "/INT") (class "Default")
      (node (ref "J4") (pin "8") (pinfunction "8_8") (pintype "passive"))
    )
    (net (code "10") (name "/INT1") (class "Default")
      (node (ref "J5") (pin "7") (pinfunction "7_7") (pintype "passive"))
    )
    (net (code "11") (name "/OUT1+") (class "Default")
      (node (ref "C42") (pin "2") (pinfunction "2_2") (pintype "passive"))
      (node (ref "J2") (pin "2") (pinfunction "2_2") (pintype "passive"))
      (node (ref "U8") (pin "2") (pinfunction "OUT1_2") (pintype "passive"))
    )
    (net (code "12") (name "/OUT1-") (class "Default")
      (node (ref "C42") (pin "1") (pinfunction "1_1") (pintype "passive"))
      (node (ref "J2") (pin "1") (pinfunction "1_1") (pintype "passive"))
      (node (ref "U8") (pin "3") (pinfunction "OUT2_3") (pintype "passive"))
    )
    (net (code "13") (name "/OUT2+") (class "Default")
      (node (ref "C50") (pin "2") (pinfunction "2_2") (pintype "passive"))
      (node (ref "J3") (pin "2") (pinfunction "2_2") (pintype "passive"))
      (node (ref "U9") (pin "2") (pinfunction "OUT1_2") (pintype "passive"))
    )
    (net (code "14") (name "/OUT2-") (class "Default")
      (node (ref "C50") (pin "1") (pinfunction "1_1") (pintype "passive"))
      (node (ref "J3") (pin "1") (pinfunction "1_1") (pintype "passive"))
      (node (ref "U9") (pin "3") (pinfunction "OUT2_3") (pintype "passive"))
    )
    (net (code "15") (name "/P0.0") (class "Default")
      (node (ref "P2") (pin "1") (pinfunction "1_1") (pintype "passive"))
      (node (ref "U1") (pin "39") (pinfunction "RxD3/ADC8/AD0/P0.0_39") (pintype "passive"))
    )
    (net (code "16") (name "/P0.1") (class "Default")
      (node (ref "P2") (pin "2") (pinfunction "2_2") (pintype "passive"))
      (node (ref "U1") (pin "40") (pinfunction "TxD3/ADC9/AD1/P0.1_40") (pintype "passive"))
    )
    (net (code "17") (name "/P0.2") (class "Default")
      (node (ref "P2") (pin "3") (pinfunction "3_3") (pintype "passive"))
      (node (ref "U1") (pin "41") (pinfunction "RxD4/ADC10/AD2/P0.2_41") (pintype "passive"))
    )
    (net (code "18") (name "/P0.3") (class "Default")
      (node (ref "P2") (pin "4") (pinfunction "4_4") (pintype "passive"))
      (node (ref "U1") (pin "43") (pinfunction "TxD_4/ADC11/AD3/P0.3_43") (pintype "passive"))
    )
    (net (code "19") (name "/P0.4(T3)") (class "Default")
      (node (ref "R4") (pin "2") (pinfunction "2_2") (pintype "passive"))
      (node (ref "R9") (pin "2") (pinfunction "2_2") (pintype "passive"))
      (node (ref "U1") (pin "44") (pinfunction "T3/ADC12/AD4/P0.4_44") (pintype "passive"))
    )
    (net (code "20") (name "/P0.5") (class "Default")
      (node (ref "R11") (pin "2") (pinfunction "2_2") (pintype "passive"))
      (node (ref "R5") (pin "2") (pinfunction "2_2") (pintype "passive"))
      (node (ref "U1") (pin "45") (pinfunction "T3CLKO/ADC13/AD5/P0.5_45") (pintype "passive"))
    )
    (net (code "21") (name "/P0.6(T4)") (class "Default")
      (node (ref "R3") (pin "2") (pinfunction "2_2") (pintype "passive"))
      (node (ref "R8") (pin "2") (pinfunction "2_2") (pintype "passive"))
      (node (ref "U1") (pin "46") (pinfunction "T4/ADC14/AD6/P0.6_46") (pintype "passive"))
    )
    (net (code "22") (name "/P1.0（PWM1）") (class "Default")
      (node (ref "R40") (pin "1") (pinfunction "1_1") (pintype "passive"))
      (node (ref "U1") (pin "48") (pinfunction "RxD2/PWM0_2/ADC0/P1.0_48") (pintype "passive"))
    )
    (net (code "23") (name "/P1.1") (class "Default")
      (node (ref "P2") (pin "5") (pinfunction "5_5") (pintype "passive"))
      (node (ref "U1") (pin "3") (pinfunction "P1.1/ADC1/PWM1_2/TxD2_3") (pintype "passive"))
    )
    (net (code "24") (name "/P1.2") (class "Default")
      (node (ref "P6") (pin "2") (pinfunction "2_2") (pintype "passive"))
      (node (ref "U1") (pin "4") (pinfunction "P1.2/ADC2/PWM2_2/SS/T2/ECI_4") (pintype "passive"))
    )
    (net (code "25") (name "/P1.3") (class "Default")
      (node (ref "P7") (pin "1") (pinfunction "1_1") (pintype "passive"))
      (node (ref "U1") (pin "5") (pinfunction "P1.3/ADC3/PWM3_2/MOSI/TC2LKO_5") (pintype "passive"))
    )
    (net (code "26") (name "/P2.0") (class "Default")
      (node (ref "R49") (pin "2") (pinfunction "2_2") (pintype "passive"))
      (node (ref "U1") (pin "30") (pinfunction "RSTSV/PWM0/A8/P2.0_30") (pintype "passive"))
      (node (ref "key2") (pin "1") (pinfunction "1_1") (pintype "passive"))
    )
    (net (code "27") (name "/P2.1") (class "Default")
      (node (ref "D3") (pin "2") (pinfunction "K_2") (pintype "passive"))
      (node (ref "U1") (pin "32") (pinfunction "PWM1/A9/P2.1_32") (pintype "passive"))
    )
    (net (code "28") (name "/P2.2（PWM4）") (class "Default")
      (node (ref "R47") (pin "1") (pinfunction "1_1") (pintype "passive"))
      (node (ref "U1") (pin "33") (pinfunction "ECI_2/SS_2/PWM2/A10/P2.2_33") (pintype "passive"))
    )
    (net (code "29") (name "/P2.3") (class "Default")
      (node (ref "P7") (pin "2") (pinfunction "2_2") (pintype "passive"))
      (node (ref "U1") (pin "34") (pinfunction "CCP0_2/MOSI_2/PWM3/A11/P2.3_34") (pintype "passive"))
    )
    (net (code "30") (name "/P2.4（PWM3）") (class "Default")
      (node (ref "R48") (pin "1") (pinfunction "1_1") (pintype "passive"))
      (node (ref "U1") (pin "35") (pinfunction "CCP1_2/I2CSDA_2/MISO_2/PWM4/A12/P2.4_35") (pintype "passive"))
    )
    (net (code "31") (name "/P2.5") (class "Default")
      (node (ref "P7") (pin "3") (pinfunction "3_3") (pintype "passive"))
      (node (ref "U1") (pin "36") (pinfunction "CCP2_2/I2CSCL_2/SCLK_2/PWM5/A13/P2.5_36") (pintype "passive"))
    )
    (net (code "32") (name "/P2.6（PWM2）") (class "Default")
      (node (ref "R39") (pin "1") (pinfunction "1_1") (pintype "passive"))
      (node (ref "U1") (pin "37") (pinfunction "CCP3_2/PWM6/A14/P2.6_37") (pintype "passive"))
    )
    (net (code "33") (name "/P2.7") (class "Default")
      (node (ref "R12") (pin "2") (pinfunction "2_2") (pintype "passive"))
      (node (ref "R6") (pin "2") (pinfunction "2_2") (pintype "passive"))
      (node (ref "U1") (pin "38") (pinfunction "PWM7/A15/P2.7_38") (pintype "passive"))
    )
    (net (code "34") (name "/P3.6") (class "Default")
      (node (ref "P6") (pin "1") (pinfunction "1_1") (pintype "passive"))
      (node (ref "U1") (pin "27") (pinfunction "CMP-/RxD_2/WR_2/INT2/P3.6_27") (pintype "passive"))
    )
    (net (code "35") (name "/P3.7（INT3）干簧管") (class "Default")
      (node (ref "P3") (pin "2") (pinfunction "2_2") (pintype "passive"))
      (node (ref "U1") (pin "28") (pinfunction "CMP+/TxD_2/RD_2/INT3/P3.7_28") (pintype "passive"))
    )
    (net (code "36") (name "/P4.3") (class "Default")
      (node (ref "R52") (pin "2") (pinfunction "2_2") (pintype "passive"))
      (node (ref "U1") (pin "42") (pinfunction "RxD_4/WR/P4.3_42") (pintype "passive"))
    )
    (net (code "37") (name "/P5.2") (class "Default")
      (node (ref "R51") (pin "2") (pinfunction "2_2") (pintype "passive"))
      (node (ref "U1") (pin "1") (pinfunction "P5.2/RxD4_2_1") (pintype "passive"))
      (node (ref "key4") (pin "1") (pinfunction "1_1") (pintype "passive"))
    )
    (net (code "38") (name "/P5.3") (class "Default")
      (node (ref "R50") (pin "2") (pinfunction "2_2") (pintype "passive"))
      (node (ref "U1") (pin "2") (pinfunction "P5.3/TxD4_2_2") (pintype "passive"))
      (node (ref "key3") (pin "1") (pinfunction "1_1") (pintype "passive"))
    )
    (net (code "39") (name "/REST") (class "Default")
      (node (ref "C5") (pin "1") (pinfunction "1_1") (pintype "passive"))
      (node (ref "R16") (pin "2") (pinfunction "2_2") (pintype "passive"))
      (node (ref "U1") (pin "14") (pinfunction "P5.4/RST/MCLKO_14") (pintype "passive"))
      (node (ref "key1") (pin "1") (pinfunction "1_1") (pintype "passive"))
    )
    (net (code "40") (name "/RX") (class "Default")
      (node (ref "P5") (pin "3") (pinfunction "3_3") (pintype "passive"))
      (node (ref "U1") (pin "25") (pinfunction "RxD3_2/P5.0_25") (pintype "passive"))
    )
    (net (code "41") (name "/RXD") (class "Default")
      (node (ref "R32") (pin "2") (pinfunction "2_2") (pintype "passive"))
      (node (ref "U1") (pin "20") (pinfunction "P3.1/TxD/CCP2_4_20") (pintype "passive"))
    )
    (net (code "42") (name "/RXD_1") (class "Default")
      (node (ref "PPS3") (pin "2") (pinfunction "2_2") (pintype "passive"))
      (node (ref "R32") (pin "1") (pinfunction "1_1") (pintype "passive"))
      (node (ref "U6") (pin "7") (pinfunction "RXD_7") (pintype "passive"))
    )
    (net (code "43") (name "/SA0{slash}SD0") (class "Default")
      (node (ref "J5") (pin "5") (pinfunction "5_5") (pintype "passive"))
      (node (ref "R10") (pin "2") (pinfunction "2_2") (pintype "passive"))
      (node (ref "R14") (pin "2") (pinfunction "2_2") (pintype "passive"))
      (node (ref "U1") (pin "22") (pinfunction "P3.3/INT1/CCP0_4/MIS0_4/I2CSDA_4_22") (pintype "passive"))
    )
    (net (code "44") (name "/SCL") (class "Default")
      (node (ref "OLED1") (pin "3") (pinfunction "3_3") (pintype "passive"))
      (node (ref "R1") (pin "2") (pinfunction "2_2") (pintype "passive"))
      (node (ref "U1") (pin "8") (pinfunction "P1.5/ADC5/PWM5_2/SCLK/I2CSCL/CCP2_8") (pintype "passive"))
    )
    (net (code "45") (name "/SCL-1") (class "Default")
      (node (ref "J5") (pin "3") (pinfunction "3_3") (pintype "passive"))
      (node (ref "R13") (pin "2") (pinfunction "2_2") (pintype "passive"))
      (node (ref "R7") (pin "2") (pinfunction "2_2") (pintype "passive"))
      (node (ref "U1") (pin "21") (pinfunction "P3.2/INT0/CCP1_4/SCLK_4/I2CSCL_4_21") (pintype "passive"))
    )
    (net (code "46") (name "/SDA") (class "Default")
      (node (ref "OLED1") (pin "4") (pinfunction "4_4") (pintype "passive"))
      (node (ref "R2") (pin "2") (pinfunction "2_2") (pintype "passive"))
      (node (ref "U1") (pin "6") (pinfunction "P1.4/ADC4/PWM4_2/MISO/I2CSDA/CCP3_6") (pintype "passive"))
    )
    (net (code "47") (name "/SDA{slash}SDI") (class "Default")
      (node (ref "J5") (pin "4") (pinfunction "4_4") (pintype "passive"))
      (node (ref "U1") (pin "23") (pinfunction "P3.4/T0/T1CLKO/MOSI_4/CMPO_23") (pintype "passive"))
    )
    (net (code "48") (name "/TX") (class "Default")
      (node (ref "P5") (pin "2") (pinfunction "2_2") (pintype "passive"))
      (node (ref "U1") (pin "26") (pinfunction "TxD3_2/P5.1_26") (pintype "passive"))
    )
    (net (code "49") (name "/TXD") (class "Default")
      (node (ref "D1") (pin "1") (pintype "passive"))
      (node (ref "U1") (pin "19") (pinfunction "P3.0/RxD/CCP3_4/INT4_19") (pintype "passive"))
    )
    (net (code "50") (name "/TXD_1") (class "Default")
      (node (ref "D1") (pin "2") (pintype "passive"))
      (node (ref "PPS2") (pin "2") (pinfunction "2_2") (pintype "passive"))
      (node (ref "U6") (pin "6") (pinfunction "TXD_6") (pintype "passive"))
    )
    (net (code "51") (name "/T_VIN") (class "Default")
      (node (ref "J6") (pin "1") (pinfunction "1_1") (pintype "passive"))
      (node (ref "J7") (pin "1") (pinfunction "1_1") (pintype "passive"))
    )
    (net (code "52") (name "/USB D+") (class "Default")
      (node (ref "R30") (pin "2") (pinfunction "2_2") (pintype "passive"))
      (node (ref "U6") (pin "1") (pinfunction "UD+_1") (pintype "passive"))
    )
    (net (code "53") (name "/USB D-") (class "Default")
      (node (ref "R28") (pin "2") (pinfunction "2_2") (pintype "passive"))
      (node (ref "U6") (pin "2") (pinfunction "UD-_2") (pintype "passive"))
    )
    (net (code "54") (name "/V_SNS") (class "Default")
      (node (ref "C44") (pin "1") (pinfunction "1_1") (pintype "passive"))
      (node (ref "R43") (pin "1") (pinfunction "1_1") (pintype "passive"))
      (node (ref "R45") (pin "2") (pinfunction "2_2") (pintype "passive"))
      (node (ref "U7") (pin "7") (pinfunction "V_SNS_7") (pintype "passive"))
    )
    (net (code "55") (name "/Vref+") (class "Default")
      (node (ref "C7") (pin "1") (pinfunction "1_1") (pintype "passive"))
      (node (ref "R18") (pin "2") (pinfunction "2_2") (pintype "passive"))
      (node (ref "U1") (pin "12") (pinfunction "AVref_12") (pintype "passive"))
      (node (ref "U2") (pin "1") (pinfunction "C_1") (pintype "passive"))
      (node (ref "U2") (pin "2") (pinfunction "R_2") (pintype "passive"))
    )
    (net (code "56") (name "/XCL") (class "Default")
      (node (ref "J4") (pin "6") (pinfunction "6_6") (pintype "passive"))
    )
    (net (code "57") (name "/XDA") (class "Default")
      (node (ref "J4") (pin "5") (pinfunction "5_5") (pintype "passive"))
    )
    (net (code "58") (name "/XTAL0") (class "Default")
      (node (ref "C1") (pin "1") (pinfunction "1_1") (pintype "passive"))
      (node (ref "U1") (pin "9") (pinfunction "P1.6/ADC6/RxD_3/PWM6_2/XTALO/MCLKO_2/CCP1_9") (pintype "passive"))
      (node (ref "Y1") (pin "2") (pinfunction "OSC2_2") (pintype "passive"))
    )
    (net (code "59") (name "/XTAL1") (class "Default")
      (node (ref "C2") (pin "1") (pinfunction "1_1") (pintype "passive"))
      (node (ref "U1") (pin "10") (pinfunction "P1.7/ADC7/TxD_3/PWM7_2/XTALI/CCP0_10") (pintype "passive"))
      (node (ref "Y1") (pin "1") (pinfunction "OSC1_1") (pintype "passive"))
    )
    (net (code "60") (name "5V-VCC") (class "Default")
      (node (ref "C32") (pin "2") (pinfunction "2_2") (pintype "passive"))
      (node (ref "D4") (pin "2") (pinfunction "K_2") (pintype "passive"))
      (node (ref "S1") (pin "3") (pinfunction "3_3") (pintype "passive"))
      (node (ref "U5") (pin "1") (pinfunction "IN_1") (pintype "passive"))
    )
    (net (code "61") (name "AVCC") (class "Default")
      (node (ref "C8") (pin "1") (pinfunction "1_1") (pintype "passive"))
      (node (ref "C9") (pin "1") (pinfunction "1_1") (pintype "passive"))
      (node (ref "R17") (pin "2") (pinfunction "2_2") (pintype "passive"))
      (node (ref "R18") (pin "1") (pinfunction "1_1") (pintype "passive"))
      (node (ref "U1") (pin "13") (pinfunction "ADC_AVcc_13") (pintype "passive"))
    )
    (net (code "62") (name "GND") (class "Default")
      (node (ref "C1") (pin "2") (pinfunction "2_2") (pintype "passive"))
      (node (ref "C11") (pin "1") (pinfunction "1_1") (pintype "passive"))
      (node (ref "C12") (pin "1") (pinfunction "1_1") (pintype "passive"))
      (node (ref "C14") (pin "1") (pinfunction "1_1") (pintype "passive"))
      (node (ref "C15") (pin "1") (pinfunction "1_1") (pintype "passive"))
      (node (ref "C16") (pin "1") (pinfunction "1_1") (pintype "passive"))
      (node (ref "C17") (pin "1") (pinfunction "1_1") (pintype "passive"))
      (node (ref "C18") (pin "2") (pinfunction "2_2") (pintype "passive"))
      (node (ref "C19") (pin "2") (pinfunction "2_2") (pintype "passive"))
      (node (ref "C2") (pin "2") (pinfunction "2_2") (pintype "passive"))
      (node (ref "C20") (pin "2") (pinfunction "2_2") (pintype "passive"))
      (node (ref "C21") (pin "2") (pinfunction "2_2") (pintype "passive"))
      (node (ref "C22") (pin "2") (pinfunction "2_2") (pintype "passive"))
      (node (ref "C23") (pin "2") (pinfunction "2_2") (pintype "passive"))
      (node (ref "C24") (pin "1") (pinfunction "1_1") (pintype "passive"))
      (node (ref "C25") (pin "2") (pinfunction "2_2") (pintype "passive"))
      (node (ref "C26") (pin "1") (pinfunction "1_1") (pintype "passive"))
      (node (ref "C27") (pin "2") (pinfunction "GND_2") (pintype "passive"))
      (node (ref "C28") (pin "1") (pinfunction "1_1") (pintype "passive"))
      (node (ref "C29") (pin "2") (pinfunction "2_2") (pintype "passive"))
      (node (ref "C3") (pin "1") (pinfunction "1_1") (pintype "passive"))
      (node (ref "C30") (pin "2") (pinfunction "2_2") (pintype "passive"))
      (node (ref "C31") (pin "1") (pinfunction "1_1") (pintype "passive"))
      (node (ref "C32") (pin "1") (pinfunction "1_1") (pintype "passive"))
      (node (ref "C33") (pin "1") (pinfunction "1_1") (pintype "passive"))
      (node (ref "C34") (pin "1") (pinfunction "1_1") (pintype "passive"))
      (node (ref "C36") (pin "2") (pinfunction "2_2") (pintype "passive"))
      (node (ref "C37") (pin "2") (pinfunction "2_2") (pintype "passive"))
      (node (ref "C38") (pin "1") (pinfunction "1_1") (pintype "passive"))
      (node (ref "C39") (pin "1") (pinfunction "1_1") (pintype "passive"))
      (node (ref "C4") (pin "1") (pinfunction "1_1") (pintype "passive"))
      (node (ref "C40") (pin "2") (pinfunction "2_2") (pintype "passive"))
      (node (ref "C41") (pin "1") (pinfunction "1_1") (pintype "passive"))
      (node (ref "C43") (pin "1") (pinfunction "1_1") (pintype "passive"))
      (node (ref "C45") (pin "1") (pinfunction "1_1") (pintype "passive"))
      (node (ref "C46") (pin "1") (pinfunction "1_1") (pintype "passive"))
      (node (ref "C47") (pin "1") (pinfunction "1_1") (pintype "passive"))
      (node (ref "C48") (pin "2") (pinfunction "2_2") (pintype "passive"))
      (node (ref "C49") (pin "2") (pinfunction "2_2") (pintype "passive"))
      (node (ref "C8") (pin "2") (pinfunction "2_2") (pintype "passive"))
      (node (ref "C9") (pin "2") (pinfunction "2_2") (pintype "passive"))
      (node (ref "D2") (pin "1") (pinfunction "A_1") (pintype "passive"))
      (node (ref "J2") (pin "4") (pinfunction "4_4") (pintype "passive"))
      (node (ref "J3") (pin "4") (pinfunction "4_4") (pintype "passive"))
      (node (ref "J4") (pin "2") (pinfunction "2_2") (pintype "passive"))
      (node (ref "J5") (pin "2") (pinfunction "2_2") (pintype "passive"))
      (node (ref "J7") (pin "2") (pinfunction "2_2") (pintype "passive"))
      (node (ref "LS1") (pin "2") (pinfunction "B_2") (pintype "passive"))
      (node (ref "OLED1") (pin "1") (pinfunction "1_1") (pintype "passive"))
      (node (ref "P1") (pin "5") (pinfunction "GND_5") (pintype "passive"))
      (node (ref "P2") (pin "6") (pinfunction "6_6") (pintype "passive"))
      (node (ref "P3") (pin "4") (pinfunction "4_4") (pintype "passive"))
      (node (ref "P4") (pin "1") (pinfunction "1_1") (pintype "passive"))
      (node (ref "P4") (pin "2") (pinfunction "2_2") (pintype "passive"))
      (node (ref "P5") (pin "4") (pinfunction "4_4") (pintype "passive"))
      (node (ref "PPS1") (pin "2") (pinfunction "2_2") (pintype "passive"))
      (node (ref "R15") (pin "2") (pinfunction "2_2") (pintype "passive"))
      (node (ref "R16") (pin "1") (pinfunction "1_1") (pintype "passive"))
      (node (ref "R19") (pin "2") (pinfunction "2_2") (pintype "passive"))
      (node (ref "R22") (pin "1") (pinfunction "1_1") (pintype "passive"))
      (node (ref "R26") (pin "2") (pinfunction "2_2") (pintype "passive"))
      (node (ref "R31") (pin "2") (pinfunction "2_2") (pintype "passive"))
      (node (ref "R36") (pin "2") (pinfunction "2_2") (pintype "passive"))
      (node (ref "R44") (pin "1") (pinfunction "1_1") (pintype "passive"))
      (node (ref "R45") (pin "1") (pinfunction "1_1") (pintype "passive"))
      (node (ref "U1") (pin "17") (pinfunction "Gnd_17") (pintype "passive"))
      (node (ref "U3") (pin "1") (pinfunction "GND_1") (pintype "passive"))
      (node (ref "U4") (pin "11") (pinfunction "NC_11") (pintype "passive"))
      (node (ref "U4") (pin "12") (pinfunction "NC_12") (pintype "passive"))
      (node (ref "U4") (pin "20") (pinfunction "AGND_20") (pintype "passive"))
      (node (ref "U4") (pin "21") (pinfunction "PGND_21") (pintype "passive"))
      (node (ref "U5") (pin "2") (pinfunction "GND_2") (pintype "passive"))
      (node (ref "U5") (pin "3") (pinfunction "/EN_3") (pintype "passive"))
      (node (ref "U6") (pin "3") (pinfunction "GND_3") (pintype "passive"))
      (node (ref "U7") (pin "15") (pinfunction "PWPD_15") (pintype "passive"))
      (node (ref "U7") (pin "2") (pinfunction "GND_2") (pintype "passive"))
      (node (ref "U7") (pin "3") (pinfunction "GND_3") (pintype "passive"))
      (node (ref "U8") (pin "4") (pinfunction "GND_4") (pintype "passive"))
      (node (ref "U9") (pin "4") (pinfunction "GND_4") (pintype "passive"))
      (node (ref "key2") (pin "2") (pinfunction "2_2") (pintype "passive"))
      (node (ref "key3") (pin "2") (pinfunction "2_2") (pintype "passive"))
      (node (ref "key4") (pin "2") (pinfunction "2_2") (pintype "passive"))
    )
    (net (code "63") (name "Net-(C10-Pad2)") (class "Default")
      (node (ref "C10") (pin "2") (pinfunction "2_2") (pintype "passive"))
      (node (ref "L2") (pin "2") (pinfunction "2_2") (pintype "passive"))
      (node (ref "R25") (pin "1") (pinfunction "1_1") (pintype "passive"))
      (node (ref "U4") (pin "4") (pinfunction "SW_4") (pintype "passive"))
      (node (ref "U4") (pin "5") (pinfunction "SW_5") (pintype "passive"))
      (node (ref "U4") (pin "6") (pinfunction "SW_6") (pintype "passive"))
      (node (ref "U4") (pin "7") (pinfunction "SW_7") (pintype "passive"))
    )
    (net (code "64") (name "Net-(C25-Pad1)") (class "Default")
      (node (ref "C25") (pin "1") (pinfunction "1_1") (pintype "passive"))
      (node (ref "R29") (pin "2") (pinfunction "2_2") (pintype "passive"))
    )
    (net (code "65") (name "Net-(C35-Pad1)") (class "Default")
      (node (ref "C35") (pin "1") (pinfunction "1_1") (pintype "passive"))
      (node (ref "L3") (pin "1") (pinfunction "1_1") (pintype "passive"))
      (node (ref "U7") (pin "11") (pinfunction "PH_11") (pintype "passive"))
      (node (ref "U7") (pin "12") (pinfunction "PH_12") (pintype "passive"))
    )
    (net (code "66") (name "Net-(C44-Pad2)") (class "Default")
      (node (ref "C44") (pin "2") (pinfunction "2_2") (pintype "passive"))
      (node (ref "R38") (pin "1") (pinfunction "1_1") (pintype "passive"))
      (node (ref "R43") (pin "2") (pinfunction "2_2") (pintype "passive"))
    )
    (net (code "67") (name "Net-(C47-Pad2)") (class "Default")
      (node (ref "C47") (pin "2") (pinfunction "2_2") (pintype "passive"))
      (node (ref "R41") (pin "1") (pinfunction "1_1") (pintype "passive"))
    )
    (net (code "68") (name "Net-(D2-K)") (class "Default")
      (node (ref "D2") (pin "2") (pinfunction "K_2") (pintype "passive"))
      (node (ref "LS1") (pin "1") (pinfunction "A_1") (pintype "passive"))
      (node (ref "R53") (pin "2") (pinfunction "2_2") (pintype "passive"))
    )
    (net (code "69") (name "Net-(D3-A)") (class "Default")
      (node (ref "D3") (pin "1") (pinfunction "A_1") (pintype "passive"))
      (node (ref "R54") (pin "1") (pinfunction "1_1") (pintype "passive"))
    )
    (net (code "70") (name "Net-(J2-Pad5)") (class "Default")
      (node (ref "J2") (pin "5") (pinfunction "5_5") (pintype "passive"))
      (node (ref "R8") (pin "1") (pinfunction "1_1") (pintype "passive"))
    )
    (net (code "71") (name "Net-(J2-Pad6)") (class "Default")
      (node (ref "J2") (pin "6") (pinfunction "6_6") (pintype "passive"))
      (node (ref "R11") (pin "1") (pinfunction "1_1") (pintype "passive"))
    )
    (net (code "72") (name "Net-(J3-Pad5)") (class "Default")
      (node (ref "J3") (pin "5") (pinfunction "5_5") (pintype "passive"))
      (node (ref "R9") (pin "1") (pinfunction "1_1") (pintype "passive"))
    )
    (net (code "73") (name "Net-(J3-Pad6)") (class "Default")
      (node (ref "J3") (pin "6") (pinfunction "6_6") (pintype "passive"))
      (node (ref "R12") (pin "1") (pinfunction "1_1") (pintype "passive"))
    )
    (net (code "74") (name "Net-(J4-Pad3)") (class "Default")
      (node (ref "J4") (pin "3") (pinfunction "3_3") (pintype "passive"))
      (node (ref "R13") (pin "1") (pinfunction "1_1") (pintype "passive"))
    )
    (net (code "75") (name "Net-(J4-Pad4)") (class "Default")
      (node (ref "J4") (pin "4") (pinfunction "4_4") (pintype "passive"))
      (node (ref "R14") (pin "1") (pinfunction "1_1") (pintype "passive"))
    )
    (net (code "76") (name "Net-(P1-DM)") (class "Default")
      (node (ref "P1") (pin "2") (pinfunction "DM_2") (pintype "passive"))
      (node (ref "R28") (pin "1") (pinfunction "1_1") (pintype "passive"))
    )
    (net (code "77") (name "Net-(P1-DP)") (class "Default")
      (node (ref "P1") (pin "3") (pinfunction "DP_3") (pintype "passive"))
      (node (ref "R30") (pin "1") (pinfunction "1_1") (pintype "passive"))
    )
    (net (code "78") (name "Net-(P1-VBUS)") (class "Default")
      (node (ref "F1") (pin "1") (pinfunction "1_1") (pintype "passive"))
      (node (ref "P1") (pin "1") (pinfunction "VBUS_1") (pintype "passive"))
    )
    (net (code "79") (name "Net-(PPS1-Pad1)") (class "Default")
      (node (ref "PPS1") (pin "1") (pinfunction "1_1") (pintype "passive"))
      (node (ref "R27") (pin "2") (pinfunction "2_2") (pintype "passive"))
    )
    (net (code "80") (name "Net-(PPS2-Pad1)") (class "Default")
      (node (ref "PPS2") (pin "1") (pinfunction "1_1") (pintype "passive"))
      (node (ref "R33") (pin "1") (pinfunction "1_1") (pintype "passive"))
    )
    (net (code "81") (name "Net-(PPS3-Pad1)") (class "Default")
      (node (ref "PPS3") (pin "1") (pinfunction "1_1") (pintype "passive"))
      (node (ref "R34") (pin "1") (pinfunction "1_1") (pintype "passive"))
    )
    (net (code "82") (name "Net-(Q1-B)") (class "Default")
      (node (ref "Q1") (pin "2") (pinfunction "B_2") (pintype "passive"))
      (node (ref "R52") (pin "1") (pinfunction "1_1") (pintype "passive"))
    )
    (net (code "83") (name "Net-(Q1-C)") (class "Default")
      (node (ref "Q1") (pin "3") (pinfunction "C_3") (pintype "passive"))
      (node (ref "R53") (pin "1") (pinfunction "1_1") (pintype "passive"))
    )
    (net (code "84") (name "Net-(R23-Pad1)") (class "Default")
      (node (ref "R23") (pin "1") (pinfunction "1_1") (pintype "passive"))
      (node (ref "R24") (pin "1") (pinfunction "1_1") (pintype "passive"))
    )
    (net (code "85") (name "Net-(U3-EN)") (class "Default")
      (node (ref "R20") (pin "1") (pinfunction "1_1") (pintype "passive"))
      (node (ref "U3") (pin "5") (pinfunction "EN_5") (pintype "passive"))
    )
    (net (code "86") (name "Net-(U3-SW)") (class "Default")
      (node (ref "C6") (pin "1") (pinfunction "1_1") (pintype "passive"))
      (node (ref "L1") (pin "2") (pinfunction "2_2") (pintype "passive"))
      (node (ref "U3") (pin "2") (pinfunction "SW_2") (pintype "passive"))
    )
    (net (code "87") (name "Net-(U3-VBST)") (class "Default")
      (node (ref "C6") (pin "2") (pinfunction "2_2") (pintype "passive"))
      (node (ref "U3") (pin "6") (pinfunction "VBST_6") (pintype "passive"))
    )
    (net (code "88") (name "Net-(U3-VFB)") (class "Default")
      (node (ref "C13") (pin "1") (pinfunction "1_1") (pintype "passive"))
      (node (ref "R21") (pin "1") (pinfunction "1_1") (pintype "passive"))
      (node (ref "R22") (pin "2") (pinfunction "2_2") (pintype "passive"))
      (node (ref "U3") (pin "4") (pinfunction "VFB_4") (pintype "passive"))
    )
    (net (code "89") (name "Net-(U4-BOOT)") (class "Default")
      (node (ref "C10") (pin "1") (pinfunction "1_1") (pintype "passive"))
      (node (ref "U4") (pin "8") (pinfunction "BOOT_8") (pintype "passive"))
    )
    (net (code "90") (name "Net-(U4-COMP)") (class "Default")
      (node (ref "C22") (pin "1") (pinfunction "1_1") (pintype "passive"))
      (node (ref "R29") (pin "1") (pinfunction "1_1") (pintype "passive"))
      (node (ref "U4") (pin "18") (pinfunction "COMP_18") (pintype "passive"))
    )
    (net (code "91") (name "Net-(U4-EN)") (class "Default")
      (node (ref "C28") (pin "2") (pinfunction "2_2") (pintype "passive"))
      (node (ref "U4") (pin "1") (pinfunction "VCC_1") (pintype "passive"))
      (node (ref "U4") (pin "2") (pinfunction "EN_2") (pintype "passive"))
    )
    (net (code "92") (name "Net-(U4-FB)") (class "Default")
      (node (ref "R23") (pin "2") (pinfunction "2_2") (pintype "passive"))
      (node (ref "R26") (pin "1") (pinfunction "1_1") (pintype "passive"))
      (node (ref "U4") (pin "17") (pinfunction "FB_17") (pintype "passive"))
    )
    (net (code "93") (name "Net-(U4-FSW)") (class "Default")
      (node (ref "R25") (pin "2") (pinfunction "2_2") (pintype "passive"))
      (node (ref "U4") (pin "3") (pinfunction "FSW_3") (pintype "passive"))
    )
    (net (code "94") (name "Net-(U4-ILIM)") (class "Default")
      (node (ref "R31") (pin "1") (pinfunction "1_1") (pintype "passive"))
      (node (ref "U4") (pin "19") (pinfunction "ILIM_19") (pintype "passive"))
    )
    (net (code "95") (name "Net-(U4-SS)") (class "Default")
      (node (ref "C29") (pin "1") (pinfunction "1_1") (pintype "passive"))
      (node (ref "U4") (pin "10") (pinfunction "SS_10") (pintype "passive"))
    )
    (net (code "96") (name "Net-(U5-BYPASS)") (class "Default")
      (node (ref "C33") (pin "2") (pinfunction "2_2") (pintype "passive"))
      (node (ref "U5") (pin "4") (pinfunction "BYPASS_4") (pintype "passive"))
    )
    (net (code "97") (name "Net-(U6-V3)") (class "Default")
      (node (ref "C30") (pin "1") (pinfunction "1_1") (pintype "passive"))
      (node (ref "U6") (pin "8") (pinfunction "V3_8") (pintype "passive"))
    )
    (net (code "98") (name "Net-(U7-BOOT)") (class "Default")
      (node (ref "C35") (pin "2") (pinfunction "2_2") (pintype "passive"))
      (node (ref "U7") (pin "13") (pinfunction "BOOT_13") (pintype "passive"))
    )
    (net (code "99") (name "Net-(U7-COMP)") (class "Default")
      (node (ref "C45") (pin "2") (pinfunction "2_2") (pintype "passive"))
      (node (ref "R41") (pin "2") (pinfunction "2_2") (pintype "passive"))
      (node (ref "U7") (pin "8") (pinfunction "COMP_8") (pintype "passive"))
    )
    (net (code "100") (name "Net-(U7-PWRGD)") (class "Default")
      (node (ref "R35") (pin "1") (pinfunction "1_1") (pintype "passive"))
      (node (ref "U7") (pin "14") (pinfunction "PWRGD_14") (pintype "passive"))
    )
    (net (code "101") (name "Net-(U7-RT{slash}CLK)") (class "Default")
      (node (ref "R36") (pin "1") (pinfunction "1_1") (pintype "passive"))
      (node (ref "U7") (pin "1") (pinfunction "RT/CLK_1") (pintype "passive"))
    )
    (net (code "102") (name "Net-(U7-SS{slash}TR)") (class "Default")
      (node (ref "C43") (pin "2") (pinfunction "2_2") (pintype "passive"))
      (node (ref "U7") (pin "9") (pinfunction "SS/TR_9") (pintype "passive"))
    )
    (net (code "103") (name "Net-(U8-IN1)") (class "Default")
      (node (ref "R39") (pin "2") (pinfunction "2_2") (pintype "passive"))
      (node (ref "U8") (pin "6") (pinfunction "IN1_6") (pintype "passive"))
    )
    (net (code "104") (name "Net-(U8-IN2)") (class "Default")
      (node (ref "R40") (pin "2") (pinfunction "2_2") (pintype "passive"))
      (node (ref "U8") (pin "5") (pinfunction "IN2_5") (pintype "passive"))
    )
    (net (code "105") (name "Net-(U8-NSLEEP)") (class "Default")
      (node (ref "C36") (pin "1") (pinfunction "1_1") (pintype "passive"))
      (node (ref "R37") (pin "1") (pinfunction "1_1") (pintype "passive"))
      (node (ref "U8") (pin "7") (pinfunction "NSLEEP_7") (pintype "passive"))
      (node (ref "U8") (pin "8") (pinfunction "VCC_8") (pintype "passive"))
    )
    (net (code "106") (name "Net-(U9-IN1)") (class "Default")
      (node (ref "R47") (pin "2") (pinfunction "2_2") (pintype "passive"))
      (node (ref "U9") (pin "6") (pinfunction "IN1_6") (pintype "passive"))
    )
    (net (code "107") (name "Net-(U9-IN2)") (class "Default")
      (node (ref "R48") (pin "2") (pinfunction "2_2") (pintype "passive"))
      (node (ref "U9") (pin "5") (pinfunction "IN2_5") (pintype "passive"))
    )
    (net (code "108") (name "Net-(U9-NSLEEP)") (class "Default")
      (node (ref "C48") (pin "1") (pinfunction "1_1") (pintype "passive"))
      (node (ref "R46") (pin "1") (pinfunction "1_1") (pintype "passive"))
      (node (ref "U9") (pin "7") (pinfunction "NSLEEP_7") (pintype "passive"))
      (node (ref "U9") (pin "8") (pinfunction "VCC_8") (pintype "passive"))
    )
    (net (code "109") (name "OUT-5V") (class "Default")
      (node (ref "C11") (pin "2") (pinfunction "2_2") (pintype "passive"))
      (node (ref "C12") (pin "2") (pinfunction "2_2") (pintype "passive"))
      (node (ref "C13") (pin "2") (pinfunction "2_2") (pintype "passive"))
      (node (ref "D4") (pin "1") (pinfunction "A_1") (pintype "passive"))
      (node (ref "J2") (pin "3") (pinfunction "3_3") (pintype "passive"))
      (node (ref "J3") (pin "3") (pinfunction "3_3") (pintype "passive"))
      (node (ref "L1") (pin "1") (pinfunction "1_1") (pintype "passive"))
      (node (ref "P2") (pin "7") (pinfunction "7_7") (pintype "passive"))
      (node (ref "P3") (pin "1") (pinfunction "1_1") (pintype "passive"))
      (node (ref "P4") (pin "5") (pinfunction "5_5") (pintype "passive"))
      (node (ref "P4") (pin "6") (pinfunction "6_6") (pintype "passive"))
      (node (ref "P5") (pin "5") (pinfunction "5_5") (pintype "passive"))
      (node (ref "Q1") (pin "1") (pinfunction "E_1") (pintype "passive"))
      (node (ref "R21") (pin "2") (pinfunction "2_2") (pintype "passive"))
      (node (ref "R3") (pin "1") (pinfunction "1_1") (pintype "passive"))
      (node (ref "R4") (pin "1") (pinfunction "1_1") (pintype "passive"))
      (node (ref "R5") (pin "1") (pinfunction "1_1") (pintype "passive"))
      (node (ref "R6") (pin "1") (pinfunction "1_1") (pintype "passive"))
    )
    (net (code "110") (name "POWER-MCU") (class "Default")
      (node (ref "C3") (pin "2") (pinfunction "2_2") (pintype "passive"))
      (node (ref "C31") (pin "2") (pinfunction "2_2") (pintype "passive"))
      (node (ref "C4") (pin "2") (pinfunction "2_2") (pintype "passive"))
      (node (ref "C5") (pin "2") (pinfunction "2_2") (pintype "passive"))
      (node (ref "J4") (pin "1") (pinfunction "1_1") (pintype "passive"))
      (node (ref "J5") (pin "1") (pinfunction "1_1") (pintype "passive"))
      (node (ref "OLED1") (pin "2") (pinfunction "2_2") (pintype "passive"))
      (node (ref "P4") (pin "3") (pinfunction "3_3") (pintype "passive"))
      (node (ref "P4") (pin "4") (pinfunction "4_4") (pintype "passive"))
      (node (ref "R1") (pin "1") (pinfunction "1_1") (pintype "passive"))
      (node (ref "R10") (pin "1") (pinfunction "1_1") (pintype "passive"))
      (node (ref "R17") (pin "1") (pinfunction "1_1") (pintype "passive"))
      (node (ref "R2") (pin "1") (pinfunction "1_1") (pintype "passive"))
      (node (ref "R27") (pin "1") (pinfunction "1_1") (pintype "passive"))
      (node (ref "R33") (pin "2") (pinfunction "2_2") (pintype "passive"))
      (node (ref "R34") (pin "2") (pinfunction "2_2") (pintype "passive"))
      (node (ref "R49") (pin "1") (pinfunction "1_1") (pintype "passive"))
      (node (ref "R50") (pin "1") (pinfunction "1_1") (pintype "passive"))
      (node (ref "R51") (pin "1") (pinfunction "1_1") (pintype "passive"))
      (node (ref "R54") (pin "2") (pinfunction "2_2") (pintype "passive"))
      (node (ref "R7") (pin "1") (pinfunction "1_1") (pintype "passive"))
      (node (ref "U1") (pin "15") (pinfunction "Vcc_15") (pintype "passive"))
      (node (ref "U5") (pin "5") (pinfunction "OUT_5") (pintype "passive"))
      (node (ref "key1") (pin "2") (pinfunction "2_2") (pintype "passive"))
    )
    (net (code "111") (name "VCC-CH340") (class "Default")
      (node (ref "C27") (pin "1") (pinfunction "VCC_1") (pintype "passive"))
      (node (ref "C34") (pin "2") (pinfunction "2_2") (pintype "passive"))
      (node (ref "F1") (pin "2") (pinfunction "2_2") (pintype "passive"))
      (node (ref "S1") (pin "2") (pinfunction "public_2") (pintype "passive"))
      (node (ref "U6") (pin "5") (pinfunction "VCC_5") (pintype "passive"))
    )
    (net (code "112") (name "unconnected-(J6-Pad3)") (class "Default")
      (node (ref "J6") (pin "3") (pinfunction "3_3") (pintype "passive"))
    )
    (net (code "113") (name "unconnected-(P1-ID-Pad4)") (class "Default")
      (node (ref "P1") (pin "4") (pinfunction "ID_4") (pintype "passive+no_connect"))
    )
    (net (code "114") (name "unconnected-(P3-Pad3)") (class "Default")
      (node (ref "P3") (pin "3") (pinfunction "3_3") (pintype "passive"))
    )
    (net (code "115") (name "unconnected-(P5-Pad1)") (class "Default")
      (node (ref "P5") (pin "1") (pinfunction "1_1") (pintype "passive"))
    )
    (net (code "116") (name "unconnected-(P5-Pad6)") (class "Default")
      (node (ref "P5") (pin "6") (pinfunction "6_6") (pintype "passive"))
    )
    (net (code "117") (name "unconnected-(S1-Pad1)") (class "Default")
      (node (ref "S1") (pin "1") (pinfunction "1_1") (pintype "passive+no_connect"))
    )
    (net (code "118") (name "unconnected-(U1-CMPO_2{slash}ALE{slash}P4.1-Pad29)") (class "Default")
      (node (ref "U1") (pin "29") (pinfunction "CMPO_2/ALE/P4.1_29") (pintype "passive"))
    )
    (net (code "119") (name "unconnected-(U1-P4.0{slash}WR_3{slash}RxD2_2-Pad18)") (class "Default")
      (node (ref "U1") (pin "18") (pinfunction "P4.0/WR_3/RxD2_2_18") (pintype "passive"))
    )
    (net (code "120") (name "unconnected-(U1-P4.4{slash}RD{slash}TxD_4-Pad7)") (class "Default")
      (node (ref "U1") (pin "7") (pinfunction "P4.4/RD/TxD_4_7") (pintype "passive"))
    )
    (net (code "121") (name "unconnected-(U1-P5.5-Pad16)") (class "Default")
      (node (ref "U1") (pin "16") (pinfunction "P5.5_16") (pintype "passive"))
    )
    (net (code "122") (name "unconnected-(U1-T4CLKO{slash}ADC15{slash}AD7{slash}P0.7-Pad47)") (class "Default")
      (node (ref "U1") (pin "47") (pinfunction "T4CLKO/ADC15/AD7/P0.7_47") (pintype "passive"))
    )
    (net (code "123") (name "unconnected-(U1-TxD2_2{slash}RD_3{slash}P4.2-Pad31)") (class "Default")
      (node (ref "U1") (pin "31") (pinfunction "TxD2_2/RD_3/P4.2_31") (pintype "passive"))
    )
    (net (code "124") (name "unconnected-(U4-MODE-Pad13)") (class "Default")
      (node (ref "U4") (pin "13") (pinfunction "MODE_13") (pintype "passive"))
    )
    (net (code "125") (name "unconnected-(U6-RTS#-Pad4)") (class "Default")
      (node (ref "U6") (pin "4") (pinfunction "RTS#_4") (pintype "passive+no_connect"))
    )
  )
)
